# Mode.net
KiCad netlist of a schematic drawn in Altium Designer
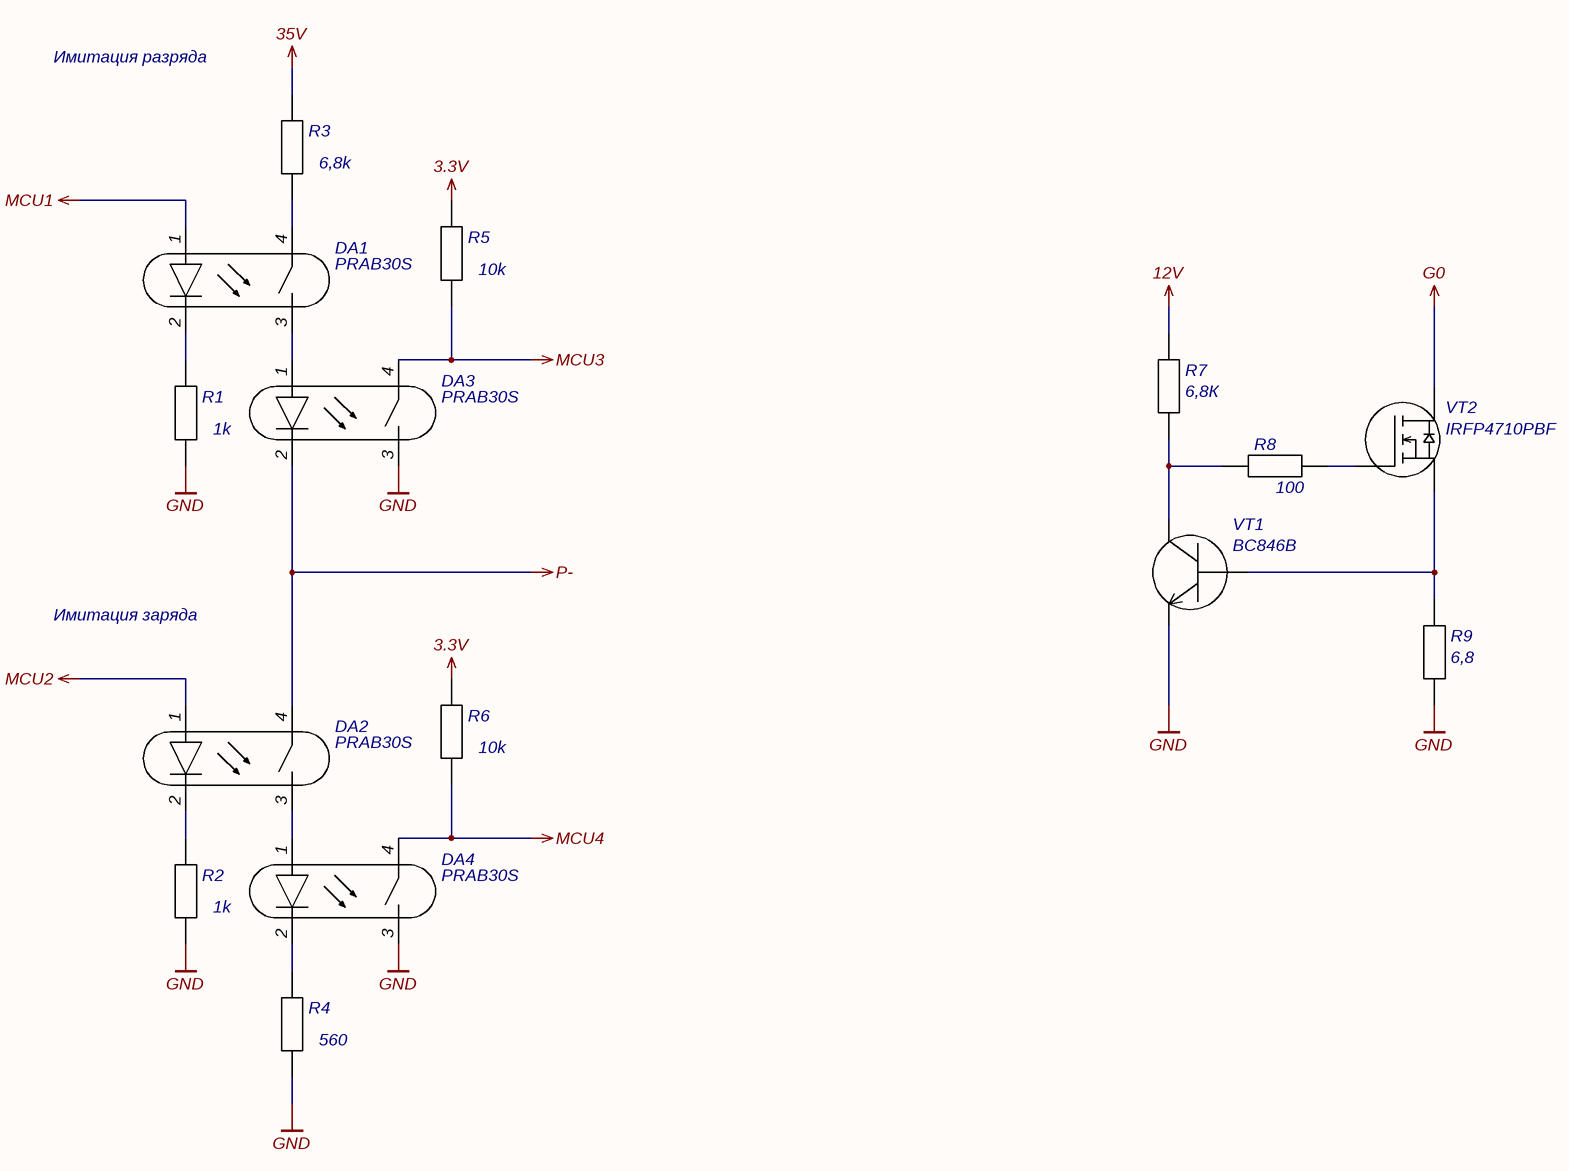
[diagram p0: Mode.SchDoc]

(export (version "E")
  (design (tool "Eeschema 10.0.6"))
  (components
    (comp (ref "DA1")
      (value "PRAB30S")
      (footprint "SOP-4")
      (description "Реле твердотельное с оптической развязкой")
      (fields (field (name "MANUFACTURER") "ОАО «Протон»"))
      (libsource (lib "Schlib") (part "PRAB30S"))
    )
    (comp (ref "DA2")
      (value "PRAB30S")
      (footprint "SOP-4")
      (description "Реле твердотельное с оптической развязкой")
      (fields (field (name "MANUFACTURER") "ОАО «Протон»"))
      (libsource (lib "Schlib") (part "PRAB30S"))
    )
    (comp (ref "DA3")
      (value "PRAB30S")
      (footprint "SOP-4")
      (description "Реле твердотельное с оптической развязкой")
      (fields (field (name "MANUFACTURER") "ОАО «Протон»"))
      (libsource (lib "Schlib") (part "PRAB30S"))
    )
    (comp (ref "DA4")
      (value "PRAB30S")
      (footprint "SOP-4")
      (description "Реле твердотельное с оптической развязкой")
      (fields (field (name "MANUFACTURER") "ОАО «Протон»"))
      (libsource (lib "Schlib") (part "PRAB30S"))
    )
    (comp (ref "R1")
      (value "1k")
      (footprint "R0603")
      (description "Чип-резистор")
      (libsource (lib "Passive") (part "Chip Resistor"))
    )
    (comp (ref "R2")
      (value "1k")
      (footprint "R0603")
      (description "Чип-резистор")
      (libsource (lib "Passive") (part "Chip Resistor"))
    )
    (comp (ref "R3")
      (value "6,8k")
      (footprint "R1206")
      (description "Чип-резистор")
      (libsource (lib "Passive") (part "Chip Resistor"))
    )
    (comp (ref "R4")
      (value "560")
      (footprint "R1206")
      (description "Чип-резистор")
      (libsource (lib "Passive") (part "Chip Resistor"))
    )
    (comp (ref "R5")
      (value "10k")
      (footprint "R0603")
      (description "Чип-резистор")
      (libsource (lib "Passive") (part "Chip Resistor"))
    )
    (comp (ref "R6")
      (value "10k")
      (footprint "R0603")
      (description "Чип-резистор")
      (libsource (lib "Passive") (part "Chip Resistor"))
    )
    (comp (ref "R7")
      (value "6,8К")
      (footprint "R1206")
      (description "Чип-резистор")
      (libsource (lib "Passive") (part "Chip Resistor"))
    )
    (comp (ref "R8")
      (value "100")
      (footprint "R0603")
      (description "Чип-резистор")
      (libsource (lib "") (part "Chip Resistor_1"))
    )
    (comp (ref "R9")
      (value "6,8")
      (footprint "SQP 5W")
      (description "Резистор")
      (libsource (lib "Passive") (part "Resistor"))
    )
    (comp (ref "VT1")
      (value "BC846B")
      (footprint "SOT-23")
      (description "Транзистор биполярный NPN, 65В")
      (fields (field (name "MANUFACTURER") "Nexperia B.V."))
      (libsource (lib "Schlib") (part "BC846B"))
    )
    (comp (ref "VT2")
      (value "IRFP4710PBF")
      (footprint "TO-247AC")
      (description "Транзистор MOSFET N-канал, 100В")
      (fields (field (name "MANUFACTURER") "INFINEON TECHNOLOGIES AG."))
      (libsource (lib "Schlib") (part "IRFP4710PBF"))
    )
  )
  (nets
    (net (code "1") (name "3.3V") (class "Default")
      (node (ref "R5") (pin "2") (pinfunction "2_2") (pintype "passive"))
      (node (ref "R6") (pin "2") (pinfunction "2_2") (pintype "passive"))
    )
    (net (code "2") (name "12V") (class "Default")
      (node (ref "R7") (pin "2") (pinfunction "2_2") (pintype "passive"))
    )
    (net (code "3") (name "35V") (class "Default")
      (node (ref "R3") (pin "2") (pinfunction "2_2") (pintype "passive"))
    )
    (net (code "4") (name "G0") (class "Default")
      (node (ref "VT2") (pin "2") (pinfunction "D_2") (pintype "passive"))
    )
    (net (code "5") (name "GND") (class "Default")
      (node (ref "DA3") (pin "3") (pinfunction "Out1.2_3") (pintype "passive"))
      (node (ref "DA4") (pin "3") (pinfunction "Out1.2_3") (pintype "passive"))
      (node (ref "R1") (pin "1") (pinfunction "1_1") (pintype "passive"))
      (node (ref "R2") (pin "1") (pinfunction "1_1") (pintype "passive"))
      (node (ref "R4") (pin "1") (pinfunction "1_1") (pintype "passive"))
      (node (ref "R9") (pin "1") (pinfunction "1_1") (pintype "passive"))
      (node (ref "VT1") (pin "2") (pinfunction "E_2") (pintype "passive"))
    )
    (net (code "6") (name "MCU1") (class "Default")
      (node (ref "DA1") (pin "1") (pinfunction "A1_1") (pintype "passive"))
    )
    (net (code "7") (name "MCU2") (class "Default")
      (node (ref "DA2") (pin "1") (pinfunction "A1_1") (pintype "passive"))
    )
    (net (code "8") (name "MCU3") (class "Default")
      (node (ref "DA3") (pin "4") (pinfunction "Out1.1_4") (pintype "passive"))
      (node (ref "R5") (pin "1") (pinfunction "1_1") (pintype "passive"))
    )
    (net (code "9") (name "MCU4") (class "Default")
      (node (ref "DA4") (pin "4") (pinfunction "Out1.1_4") (pintype "passive"))
      (node (ref "R6") (pin "1") (pinfunction "1_1") (pintype "passive"))
    )
    (net (code "10") (name "Net-(DA1-K1)") (class "Default")
      (node (ref "DA1") (pin "2") (pinfunction "K1_2") (pintype "passive"))
      (node (ref "R1") (pin "2") (pinfunction "2_2") (pintype "passive"))
    )
    (net (code "11") (name "Net-(DA1-Out1.1)") (class "Default")
      (node (ref "DA1") (pin "4") (pinfunction "Out1.1_4") (pintype "passive"))
      (node (ref "R3") (pin "1") (pinfunction "1_1") (pintype "passive"))
    )
    (net (code "12") (name "Net-(DA1-Out1.2)") (class "Default")
      (node (ref "DA1") (pin "3") (pinfunction "Out1.2_3") (pintype "passive"))
      (node (ref "DA3") (pin "1") (pinfunction "A1_1") (pintype "passive"))
    )
    (net (code "13") (name "Net-(DA2-K1)") (class "Default")
      (node (ref "DA2") (pin "2") (pinfunction "K1_2") (pintype "passive"))
      (node (ref "R2") (pin "2") (pinfunction "2_2") (pintype "passive"))
    )
    (net (code "14") (name "Net-(DA2-Out1.2)") (class "Default")
      (node (ref "DA2") (pin "3") (pinfunction "Out1.2_3") (pintype "passive"))
      (node (ref "DA4") (pin "1") (pinfunction "A1_1") (pintype "passive"))
    )
    (net (code "15") (name "Net-(DA4-K1)") (class "Default")
      (node (ref "DA4") (pin "2") (pinfunction "K1_2") (pintype "passive"))
      (node (ref "R4") (pin "2") (pinfunction "2_2") (pintype "passive"))
    )
    (net (code "16") (name "Net-(VT1-B)") (class "Default")
      (node (ref "R9") (pin "2") (pinfunction "2_2") (pintype "passive"))
      (node (ref "VT1") (pin "1") (pinfunction "B_1") (pintype "passive"))
      (node (ref "VT2") (pin "3") (pinfunction "S_3") (pintype "passive"))
    )
    (net (code "17") (name "Net-(VT1-C)") (class "Default")
      (node (ref "R7") (pin "1") (pinfunction "1_1") (pintype "passive"))
      (node (ref "R8") (pin "1") (pinfunction "1_1") (pintype "passive"))
      (node (ref "VT1") (pin "3") (pinfunction "C_3") (pintype "passive"))
    )
    (net (code "18") (name "Net-(VT2-G)") (class "Default")
      (node (ref "R8") (pin "2") (pinfunction "2_2") (pintype "passive"))
      (node (ref "VT2") (pin "1") (pinfunction "G_1") (pintype "passive"))
    )
    (net (code "19") (name "P-") (class "Default")
      (node (ref "DA2") (pin "4") (pinfunction "Out1.1_4") (pintype "passive"))
      (node (ref "DA3") (pin "2") (pinfunction "K1_2") (pintype "passive"))
    )
  )
)
